# Servo_LED.net
KiCad netlist of a schematic drawn in EAGLE
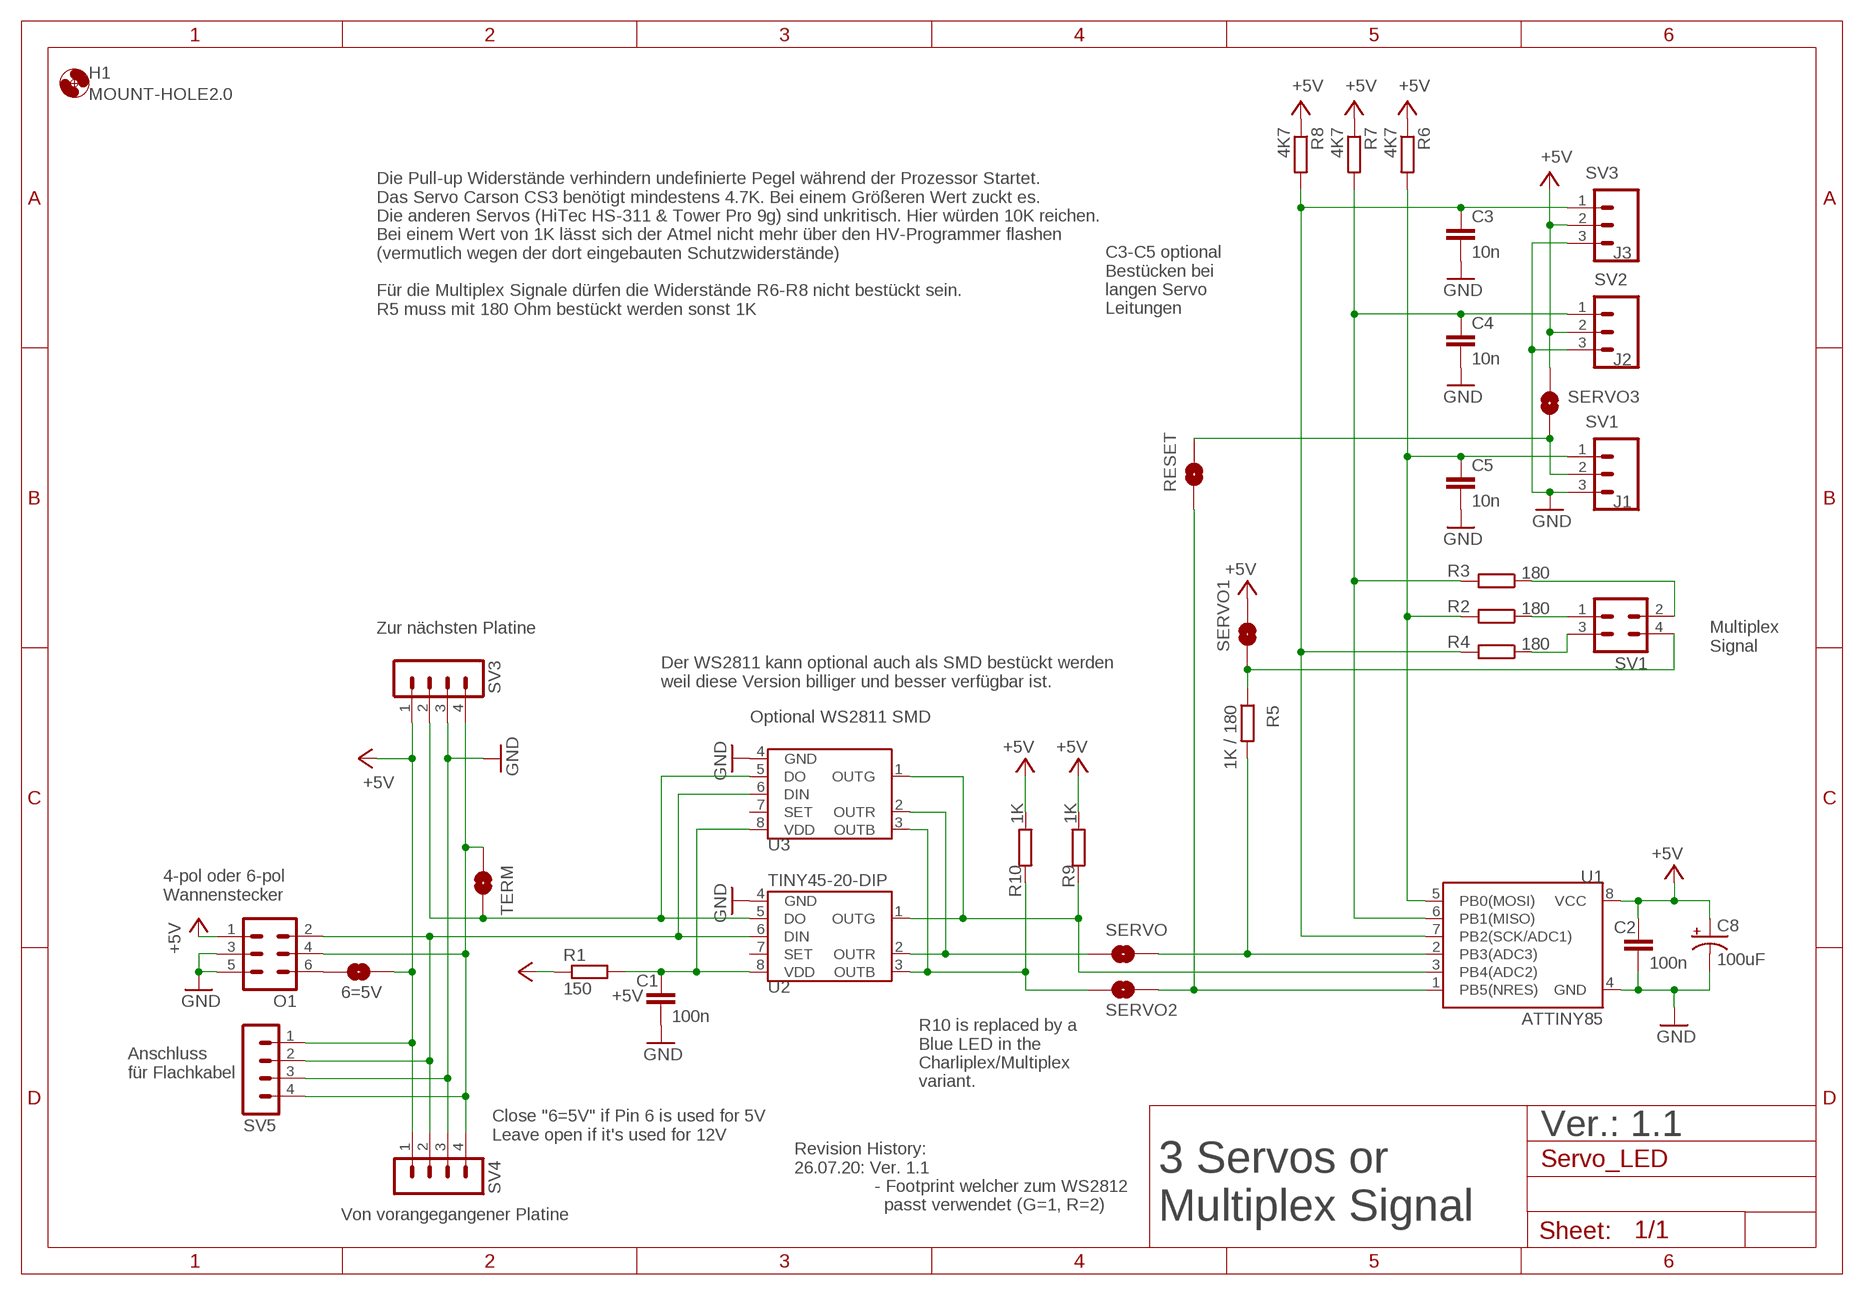
[diagram p0: schematic, sheet 1]

(export (version "E")
  (design (tool "Eeschema 10.0.6"))
  (components
    (comp (ref "6=5V")
      (value "SOLDERJUMPERNO")
      (footprint "eagle-import:SJ_2S-NO")
      (libsource (lib "eagle-import") (part "SOLDERJUMPERNO"))
    )
    (comp (ref "C1")
      (value "100n")
      (footprint "eagle-import:C025-024X044")
      (libsource (lib "eagle-import") (part "C-EU025-024X044"))
    )
    (comp (ref "C2")
      (value "100n")
      (footprint "eagle-import:C025-024X044")
      (libsource (lib "eagle-import") (part "C-EU025-024X044"))
    )
    (comp (ref "C3")
      (value "10n")
      (footprint "eagle-import:C0805")
      (libsource (lib "eagle-import") (part "C-EUC0805"))
    )
    (comp (ref "C4")
      (value "10n")
      (footprint "eagle-import:C0805")
      (libsource (lib "eagle-import") (part "C-EUC0805"))
    )
    (comp (ref "C5")
      (value "10n")
      (footprint "eagle-import:C0805")
      (libsource (lib "eagle-import") (part "C-EUC0805"))
    )
    (comp (ref "C8")
      (value "100uF")
      (footprint "eagle-import:SPARKFUN-CAPACITORS_CPOL-RADIAL-100UF-25V")
      (libsource (lib "eagle-import") (part "SPARKFUN-CAPACITORS_100UF-25V-20%(PTH)"))
    )
    (comp (ref "H1")
      (value "MOUNT-HOLE2.0")
      (footprint "eagle-import:2,0")
      (libsource (lib "eagle-import") (part "MOUNT-HOLE2.0"))
    )
    (comp (ref "J1")
      (value "SV1")
      (footprint "eagle-import:1X03")
      (libsource (lib "eagle-import") (part "M03PTH"))
    )
    (comp (ref "J2")
      (value "SV2")
      (footprint "eagle-import:1X03")
      (libsource (lib "eagle-import") (part "M03PTH"))
    )
    (comp (ref "J3")
      (value "SV3")
      (footprint "eagle-import:1X03")
      (libsource (lib "eagle-import") (part "M03PTH"))
    )
    (comp (ref "O1")
      (value "ML6")
      (footprint "eagle-import:ML6")
      (libsource (lib "eagle-import") (part "ML6"))
    )
    (comp (ref "R1")
      (value "150")
      (footprint "eagle-import:RCL_0207_2V")
      (libsource (lib "eagle-import") (part "RCL_R-EU_0207/2V"))
    )
    (comp (ref "R2")
      (value "180")
      (footprint "eagle-import:RCL_0207_2V")
      (libsource (lib "eagle-import") (part "RCL_R-EU_0207/2V"))
    )
    (comp (ref "R3")
      (value "180")
      (footprint "eagle-import:RCL_0207_2V")
      (libsource (lib "eagle-import") (part "RCL_R-EU_0207/2V"))
    )
    (comp (ref "R4")
      (value "180")
      (footprint "eagle-import:RCL_0207_2V")
      (libsource (lib "eagle-import") (part "RCL_R-EU_0207/2V"))
    )
    (comp (ref "R5")
      (value "1K / 180")
      (footprint "eagle-import:RCL_0207_2V")
      (libsource (lib "eagle-import") (part "RCL_R-EU_0207/2V"))
    )
    (comp (ref "R6")
      (value "4K7")
      (footprint "eagle-import:RCL_0207_2V")
      (libsource (lib "eagle-import") (part "RCL_R-EU_0207/2V"))
    )
    (comp (ref "R7")
      (value "4K7")
      (footprint "eagle-import:RCL_0207_2V")
      (libsource (lib "eagle-import") (part "RCL_R-EU_0207/2V"))
    )
    (comp (ref "R8")
      (value "4K7")
      (footprint "eagle-import:RCL_0207_2V")
      (libsource (lib "eagle-import") (part "RCL_R-EU_0207/2V"))
    )
    (comp (ref "R9")
      (value "1K")
      (footprint "eagle-import:RCL_0207_2V")
      (libsource (lib "eagle-import") (part "RCL_R-EU_0207/2V"))
    )
    (comp (ref "R10")
      (value "1K")
      (footprint "eagle-import:RCL_0207_2V")
      (libsource (lib "eagle-import") (part "RCL_R-EU_0207/2V"))
    )
    (comp (ref "RESET")
      (value "SOLDERJUMPERNO")
      (footprint "eagle-import:SJ_2S-NO")
      (libsource (lib "eagle-import") (part "SOLDERJUMPERNO"))
    )
    (comp (ref "SERVO")
      (value "SOLDERJUMPERNO")
      (footprint "eagle-import:SJ_2S-NO")
      (libsource (lib "eagle-import") (part "SOLDERJUMPERNO"))
    )
    (comp (ref "SERVO1")
      (value "SOLDERJUMPERNO")
      (footprint "eagle-import:SJ_2S-NO")
      (libsource (lib "eagle-import") (part "SOLDERJUMPERNO"))
    )
    (comp (ref "SERVO2")
      (value "SOLDERJUMPERNO")
      (footprint "eagle-import:SJ_2S-NO")
      (libsource (lib "eagle-import") (part "SOLDERJUMPERNO"))
    )
    (comp (ref "SERVO3")
      (value "SOLDERJUMPERNO")
      (footprint "eagle-import:SJ_2S-NO")
      (libsource (lib "eagle-import") (part "SOLDERJUMPERNO"))
    )
    (comp (ref "SV1")
      (value "MA02-2MUX-SIGNAL")
      (footprint "eagle-import:MUX-SIGNAL")
      (libsource (lib "eagle-import") (part "MA02-2MUX-SIGNAL"))
    )
    (comp (ref "SV3")
      (value "MA04-1")
      (footprint "eagle-import:MA04-1")
      (libsource (lib "eagle-import") (part "MA04-1"))
    )
    (comp (ref "SV4")
      (value "MA04-1")
      (footprint "eagle-import:MA04-1")
      (libsource (lib "eagle-import") (part "MA04-1"))
    )
    (comp (ref "SV5")
      (value "MA04-1")
      (footprint "eagle-import:MA04-1")
      (libsource (lib "eagle-import") (part "MA04-1"))
    )
    (comp (ref "TERM")
      (value "SOLDERJUMPERNO")
      (footprint "eagle-import:SJ_2S-NO")
      (libsource (lib "eagle-import") (part "SOLDERJUMPERNO"))
    )
    (comp (ref "U1")
      (value "ATTINY85")
      (footprint "eagle-import:DIP08")
      (libsource (lib "eagle-import") (part "ATTINY45TINY85-20-DIP"))
    )
    (comp (ref "U2")
      (value "TINY45-20-DIP")
      (footprint "eagle-import:S3PO_MODUL_WS2811_SOUND_MP3-TF-16P_WS2811_AND_ATTINY_WS2811_DIP08")
      (libsource (lib "eagle-import") (part "S3PO_MODUL_WS2811_SOUND_MP3-TF-16P_WS2811_AND_ATTINY_WS2811-ICTINY45-20-DIP"))
    )
    (comp (ref "U3")
      (value "WS2811 SOT-8")
      (footprint "eagle-import:SOP8")
      (libsource (lib "eagle-import") (part "S3PO_MODUL_WS2811_SOUND_MP3-TF-16P_WS2811_AND_ATTINY_WS2811-ICSOP8"))
    )
  )
  (nets
    (net (code "1") (name "+5V") (class "Default")
      (node (ref "6=5V") (pin "2") (pinfunction "2_2") (pintype "passive"))
      (node (ref "C2") (pin "1") (pinfunction "1_1") (pintype "passive"))
      (node (ref "C8") (pin "1") (pinfunction "+_1") (pintype "passive"))
      (node (ref "J2") (pin "2") (pinfunction "2_2") (pintype "passive"))
      (node (ref "J3") (pin "2") (pinfunction "2_2") (pintype "passive"))
      (node (ref "O1") (pin "1") (pinfunction "1_1") (pintype "passive"))
      (node (ref "R1") (pin "1") (pinfunction "1_1") (pintype "passive"))
      (node (ref "R10") (pin "1") (pinfunction "1_1") (pintype "passive"))
      (node (ref "R6") (pin "1") (pinfunction "1_1") (pintype "passive"))
      (node (ref "R7") (pin "1") (pinfunction "1_1") (pintype "passive"))
      (node (ref "R8") (pin "1") (pinfunction "1_1") (pintype "passive"))
      (node (ref "R9") (pin "1") (pinfunction "1_1") (pintype "passive"))
      (node (ref "SERVO1") (pin "2") (pinfunction "2_2") (pintype "passive"))
      (node (ref "SERVO3") (pin "2") (pinfunction "2_2") (pintype "passive"))
      (node (ref "SV3") (pin "1") (pinfunction "1_1") (pintype "passive"))
      (node (ref "SV4") (pin "1") (pinfunction "1_1") (pintype "passive"))
      (node (ref "SV5") (pin "1") (pinfunction "1_1") (pintype "passive"))
      (node (ref "U1") (pin "8") (pinfunction "VCC_8") (pintype "bidirectional"))
    )
    (net (code "2") (name "GND") (class "Default")
      (node (ref "C1") (pin "2") (pinfunction "2_2") (pintype "passive"))
      (node (ref "C2") (pin "2") (pinfunction "2_2") (pintype "passive"))
      (node (ref "C3") (pin "2") (pinfunction "2_2") (pintype "passive"))
      (node (ref "C4") (pin "2") (pinfunction "2_2") (pintype "passive"))
      (node (ref "C5") (pin "2") (pinfunction "2_2") (pintype "passive"))
      (node (ref "C8") (pin "2") (pinfunction "-_2") (pintype "passive"))
      (node (ref "J1") (pin "3") (pinfunction "3_3") (pintype "passive"))
      (node (ref "J2") (pin "3") (pinfunction "3_3") (pintype "passive"))
      (node (ref "J3") (pin "3") (pinfunction "3_3") (pintype "passive"))
      (node (ref "O1") (pin "3") (pinfunction "3_3") (pintype "passive"))
      (node (ref "O1") (pin "5") (pinfunction "5_5") (pintype "passive"))
      (node (ref "SV3") (pin "3") (pinfunction "3_3") (pintype "passive"))
      (node (ref "SV4") (pin "3") (pinfunction "3_3") (pintype "passive"))
      (node (ref "SV5") (pin "3") (pinfunction "3_3") (pintype "passive"))
      (node (ref "U1") (pin "4") (pinfunction "GND_4") (pintype "bidirectional"))
      (node (ref "U2") (pin "4") (pinfunction "GND_4") (pintype "power_in"))
      (node (ref "U3") (pin "4") (pinfunction "GND_4") (pintype "power_in"))
    )
    (net (code "3") (name "Net-(6=5V-Pad1)") (class "Default")
      (node (ref "6=5V") (pin "1") (pinfunction "1_1") (pintype "passive"))
      (node (ref "O1") (pin "6") (pinfunction "6_6") (pintype "passive"))
    )
    (net (code "4") (name "Net-(J1-Pad2)") (class "Default")
      (node (ref "J1") (pin "2") (pinfunction "2_2") (pintype "passive"))
      (node (ref "RESET") (pin "2") (pinfunction "2_2") (pintype "passive"))
      (node (ref "SERVO3") (pin "1") (pinfunction "1_1") (pintype "passive"))
    )
    (net (code "5") (name "Net-(O1-Pad4)") (class "Default")
      (node (ref "O1") (pin "4") (pinfunction "4_4") (pintype "passive"))
      (node (ref "SV3") (pin "4") (pinfunction "4_4") (pintype "passive"))
      (node (ref "SV4") (pin "4") (pinfunction "4_4") (pintype "passive"))
      (node (ref "SV5") (pin "4") (pinfunction "4_4") (pintype "passive"))
      (node (ref "TERM") (pin "1") (pinfunction "1_1") (pintype "passive"))
    )
    (net (code "6") (name "Net-(R2-Pad1)") (class "Default")
      (node (ref "R2") (pin "1") (pinfunction "1_1") (pintype "passive"))
      (node (ref "SV1") (pin "1") (pinfunction "1_1") (pintype "passive"))
    )
    (net (code "7") (name "Net-(R3-Pad1)") (class "Default")
      (node (ref "R3") (pin "1") (pinfunction "1_1") (pintype "passive"))
      (node (ref "SV1") (pin "2") (pinfunction "2_2") (pintype "passive"))
    )
    (net (code "8") (name "Net-(R4-Pad1)") (class "Default")
      (node (ref "R4") (pin "1") (pinfunction "1_1") (pintype "passive"))
      (node (ref "SV1") (pin "3") (pinfunction "3_3") (pintype "passive"))
    )
    (net (code "9") (name "Net-(R5-Pad1)") (class "Default")
      (node (ref "R5") (pin "1") (pinfunction "1_1") (pintype "passive"))
      (node (ref "SERVO1") (pin "1") (pinfunction "1_1") (pintype "passive"))
      (node (ref "SV1") (pin "4") (pinfunction "4_4") (pintype "passive"))
    )
    (net (code "10") (name "Net-(U1-PB0(MOSI))") (class "Default")
      (node (ref "C5") (pin "1") (pinfunction "1_1") (pintype "passive"))
      (node (ref "J1") (pin "1") (pinfunction "1_1") (pintype "passive"))
      (node (ref "R2") (pin "2") (pinfunction "2_2") (pintype "passive"))
      (node (ref "R6") (pin "2") (pinfunction "2_2") (pintype "passive"))
      (node (ref "U1") (pin "5") (pinfunction "PB0(MOSI)_5") (pintype "bidirectional"))
    )
    (net (code "11") (name "Net-(U1-PB1(MISO))") (class "Default")
      (node (ref "C4") (pin "1") (pinfunction "1_1") (pintype "passive"))
      (node (ref "J2") (pin "1") (pinfunction "1_1") (pintype "passive"))
      (node (ref "R3") (pin "2") (pinfunction "2_2") (pintype "passive"))
      (node (ref "R7") (pin "2") (pinfunction "2_2") (pintype "passive"))
      (node (ref "U1") (pin "6") (pinfunction "PB1(MISO)_6") (pintype "bidirectional"))
    )
    (net (code "12") (name "Net-(U1-PB2(SCK{slash}ADC1))") (class "Default")
      (node (ref "C3") (pin "1") (pinfunction "1_1") (pintype "passive"))
      (node (ref "J3") (pin "1") (pinfunction "1_1") (pintype "passive"))
      (node (ref "R4") (pin "2") (pinfunction "2_2") (pintype "passive"))
      (node (ref "R8") (pin "2") (pinfunction "2_2") (pintype "passive"))
      (node (ref "U1") (pin "7") (pinfunction "PB2(SCK/ADC1)_7") (pintype "bidirectional"))
    )
    (net (code "13") (name "Net-(U1-PB3(ADC3))") (class "Default")
      (node (ref "R5") (pin "2") (pinfunction "2_2") (pintype "passive"))
      (node (ref "SERVO") (pin "2") (pinfunction "2_2") (pintype "passive"))
      (node (ref "U1") (pin "2") (pinfunction "PB3(ADC3)_2") (pintype "bidirectional"))
    )
    (net (code "14") (name "Net-(U1-PB4(ADC2))") (class "Default")
      (node (ref "R9") (pin "2") (pinfunction "2_2") (pintype "passive"))
      (node (ref "U1") (pin "3") (pinfunction "PB4(ADC2)_3") (pintype "bidirectional"))
      (node (ref "U2") (pin "1") (pinfunction "OUTG_1") (pintype "open_collector"))
      (node (ref "U3") (pin "1") (pinfunction "OUTG_1") (pintype "open_collector"))
    )
    (net (code "15") (name "Net-(U1-PB5(NRES))") (class "Default")
      (node (ref "RESET") (pin "1") (pinfunction "1_1") (pintype "passive"))
      (node (ref "SERVO2") (pin "2") (pinfunction "2_2") (pintype "passive"))
      (node (ref "U1") (pin "1") (pinfunction "PB5(NRES)_1") (pintype "bidirectional"))
    )
    (net (code "16") (name "Net-(U2-DIN)") (class "Default")
      (node (ref "O1") (pin "2") (pinfunction "2_2") (pintype "passive"))
      (node (ref "SV4") (pin "2") (pinfunction "2_2") (pintype "passive"))
      (node (ref "SV5") (pin "2") (pinfunction "2_2") (pintype "passive"))
      (node (ref "U2") (pin "6") (pinfunction "DIN_6") (pintype "input"))
      (node (ref "U3") (pin "6") (pinfunction "DIN_6") (pintype "input"))
    )
    (net (code "17") (name "Net-(U2-DO)") (class "Default")
      (node (ref "SV3") (pin "2") (pinfunction "2_2") (pintype "passive"))
      (node (ref "TERM") (pin "2") (pinfunction "2_2") (pintype "passive"))
      (node (ref "U2") (pin "5") (pinfunction "DO_5") (pintype "output"))
      (node (ref "U3") (pin "5") (pinfunction "DO_5") (pintype "output"))
    )
    (net (code "18") (name "Net-(U2-OUTB)") (class "Default")
      (node (ref "R10") (pin "2") (pinfunction "2_2") (pintype "passive"))
      (node (ref "SERVO2") (pin "1") (pinfunction "1_1") (pintype "passive"))
      (node (ref "U2") (pin "3") (pinfunction "OUTB_3") (pintype "open_collector"))
      (node (ref "U3") (pin "3") (pinfunction "OUTB_3") (pintype "open_collector"))
    )
    (net (code "19") (name "Net-(U2-OUTR)") (class "Default")
      (node (ref "SERVO") (pin "1") (pinfunction "1_1") (pintype "passive"))
      (node (ref "U2") (pin "2") (pinfunction "OUTR_2") (pintype "open_collector"))
      (node (ref "U3") (pin "2") (pinfunction "OUTR_2") (pintype "open_collector"))
    )
    (net (code "20") (name "Net-(U2-VDD)") (class "Default")
      (node (ref "C1") (pin "1") (pinfunction "1_1") (pintype "passive"))
      (node (ref "R1") (pin "2") (pinfunction "2_2") (pintype "passive"))
      (node (ref "U2") (pin "8") (pinfunction "VDD_8") (pintype "power_in"))
      (node (ref "U3") (pin "8") (pinfunction "VDD_8") (pintype "power_in"))
    )
    (net (code "21") (name "unconnected-(U2-SET-Pad7)") (class "Default")
      (node (ref "U2") (pin "7") (pinfunction "SET_7") (pintype "bidirectional"))
    )
    (net (code "22") (name "unconnected-(U3-SET-Pad7)") (class "Default")
      (node (ref "U3") (pin "7") (pinfunction "SET_7") (pintype "bidirectional"))
    )
  )
)
